# Ethernet.net
KiCad netlist of a schematic drawn in Altium Designer
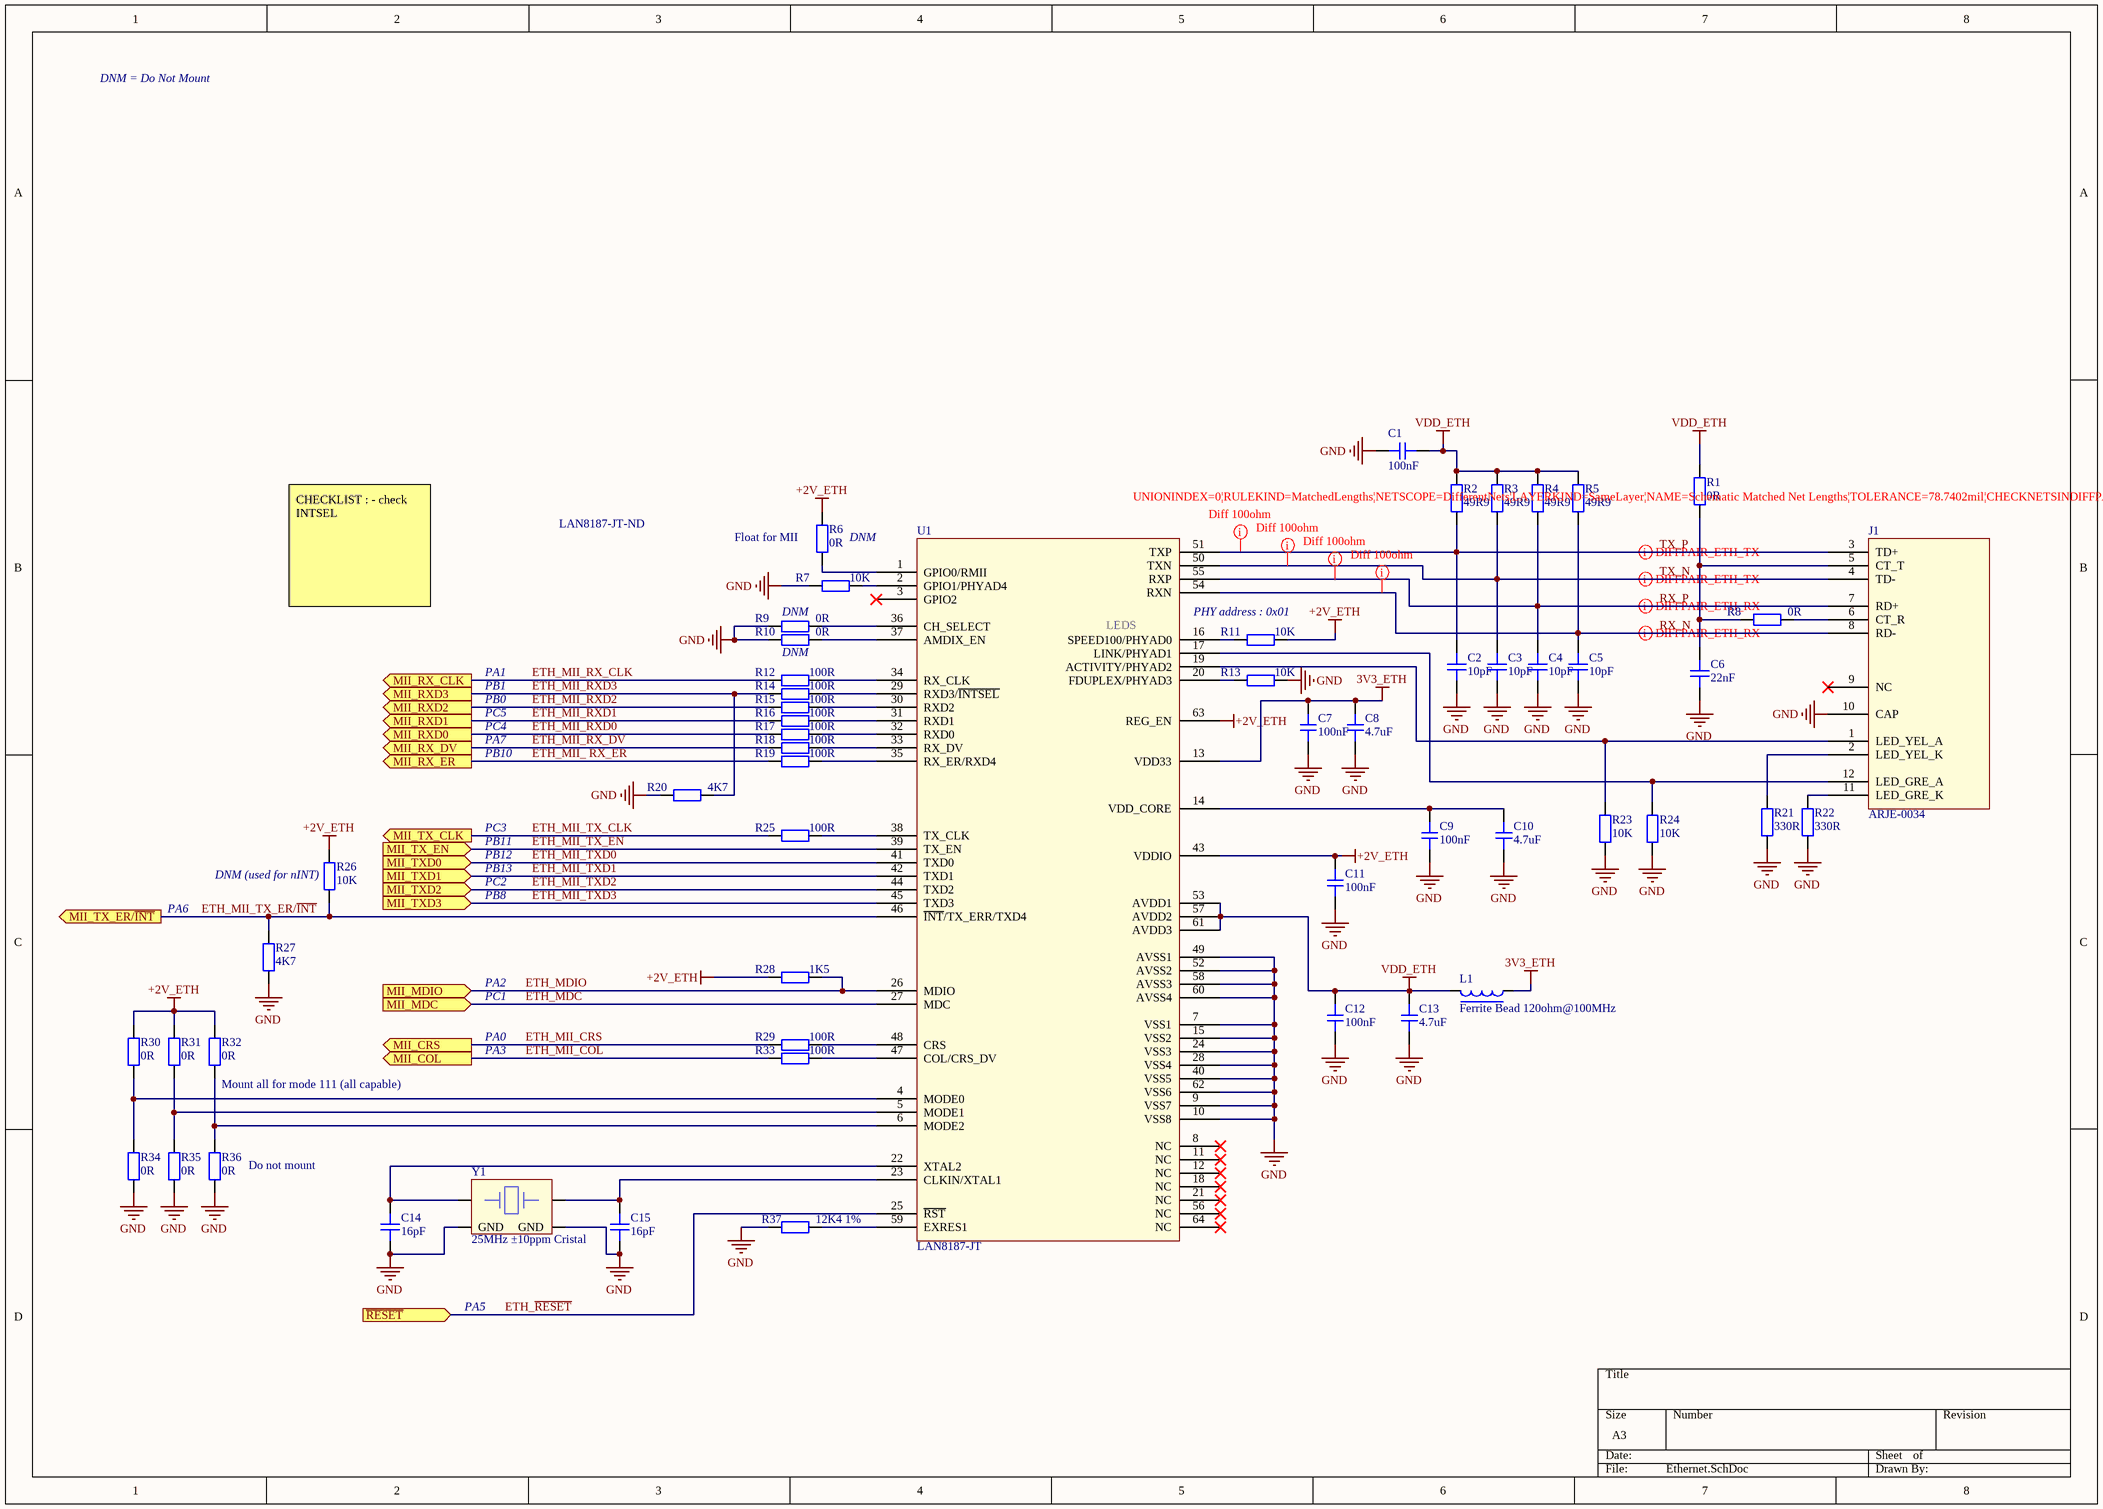
[diagram p0: Ethernet.SchDoc]

(export (version "E")
  (design (tool "Eeschema 10.0.6"))
  (components
    (comp (ref "C1")
      (value "100nF")
      (footprint "Capacitor-0603")
      (fields (field (name "Comment") "C-100nF-0603"))
      (libsource (lib "Components") (part "C-100nF-0603"))
    )
    (comp (ref "C2")
      (value "10pF")
      (footprint "Capacitor-0603")
      (fields (field (name "Comment") "C-10pF-0603"))
      (libsource (lib "Components") (part "C-10pF-0603"))
    )
    (comp (ref "C3")
      (value "10pF")
      (footprint "Capacitor-0603")
      (fields (field (name "Comment") "C-10pF-0603"))
      (libsource (lib "Components") (part "C-10pF-0603"))
    )
    (comp (ref "C4")
      (value "10pF")
      (footprint "Capacitor-0603")
      (fields (field (name "Comment") "C-10pF-0603"))
      (libsource (lib "Components") (part "C-10pF-0603"))
    )
    (comp (ref "C5")
      (value "10pF")
      (footprint "Capacitor-0603")
      (fields (field (name "Comment") "C-10pF-0603"))
      (libsource (lib "Components") (part "C-10pF-0603"))
    )
    (comp (ref "C6")
      (value "22nF")
      (footprint "Capacitor-0603")
      (fields (field (name "Comment") "C-22nF-0603"))
      (libsource (lib "Components") (part "C-22nF-0603"))
    )
    (comp (ref "C7")
      (value "100nF")
      (footprint "Capacitor-0603")
      (fields (field (name "Comment") "C-100nF-0603"))
      (libsource (lib "Components") (part "C-100nF-0603"))
    )
    (comp (ref "C8")
      (value "4.7uF")
      (footprint "Capacitor-0603")
      (fields (field (name "Comment") "C-4.7uF-0603"))
      (libsource (lib "Components") (part "C-4.7uF-0603"))
    )
    (comp (ref "C9")
      (value "100nF")
      (footprint "Capacitor-0603")
      (fields (field (name "Comment") "C-100nF-0603"))
      (libsource (lib "Components") (part "C-100nF-0603"))
    )
    (comp (ref "C10")
      (value "4.7uF")
      (footprint "Capacitor-0603")
      (fields (field (name "Comment") "C-4.7uF-0603"))
      (libsource (lib "Components") (part "C-4.7uF-0603"))
    )
    (comp (ref "C11")
      (value "100nF")
      (footprint "Capacitor-0603")
      (fields (field (name "Comment") "C-100nF-0603"))
      (libsource (lib "Components") (part "C-100nF-0603"))
    )
    (comp (ref "C12")
      (value "100nF")
      (footprint "Capacitor-0603")
      (fields (field (name "Comment") "C-100nF-0603"))
      (libsource (lib "Components") (part "C-100nF-0603"))
    )
    (comp (ref "C13")
      (value "4.7uF")
      (footprint "Capacitor-0603")
      (fields (field (name "Comment") "C-4.7uF-0603"))
      (libsource (lib "Components") (part "C-4.7uF-0603"))
    )
    (comp (ref "C14")
      (value "16pF")
      (footprint "Capacitor-0603")
      (fields (field (name "Comment") "C-16pF-0603"))
      (libsource (lib "Components") (part "C-16pF-0603"))
    )
    (comp (ref "C15")
      (value "16pF")
      (footprint "Capacitor-0603")
      (fields (field (name "Comment") "C-16pF-0603"))
      (libsource (lib "Components") (part "C-16pF-0603"))
    )
    (comp (ref "J1")
      (value "ARJE-0034")
      (footprint "ARJE-0034")
      (libsource (lib "Components") (part "ARJE-0034"))
    )
    (comp (ref "L1")
      (value "Ferrite Bead 120ohm@100MHz")
      (footprint "Inductor-0603")
      (libsource (lib "Components") (part "PE-0603PFB121ST"))
    )
    (comp (ref "R1")
      (value "0R")
      (footprint "Resistor-0603")
      (fields (field (name "Comment") "R-0R-0603"))
      (libsource (lib "Components") (part "R-0R-0603"))
    )
    (comp (ref "R2")
      (value "49R9")
      (footprint "Resistor-0603")
      (fields (field (name "Comment") "R-49R9-0603"))
      (libsource (lib "Components") (part "R-49R9-0603"))
    )
    (comp (ref "R3")
      (value "49R9")
      (footprint "Resistor-0603")
      (fields (field (name "Comment") "R-49R9-0603"))
      (libsource (lib "Components") (part "R-49R9-0603"))
    )
    (comp (ref "R4")
      (value "49R9")
      (footprint "Resistor-0603")
      (fields (field (name "Comment") "R-49R9-0603"))
      (libsource (lib "Components") (part "R-49R9-0603"))
    )
    (comp (ref "R5")
      (value "49R9")
      (footprint "Resistor-0603")
      (fields (field (name "Comment") "R-49R9-0603"))
      (libsource (lib "Components") (part "R-49R9-0603"))
    )
    (comp (ref "R6")
      (value "0R")
      (footprint "Resistor-0603")
      (fields (field (name "Comment") "R-0R-0603"))
      (libsource (lib "Components") (part "R-0R-0603"))
    )
    (comp (ref "R7")
      (value "10K")
      (footprint "Resistor-0603")
      (fields (field (name "Comment") "R-10K-0603"))
      (libsource (lib "Components") (part "R-10K-0603"))
    )
    (comp (ref "R8")
      (value "0R")
      (footprint "Resistor-0603")
      (fields (field (name "Comment") "R-0R-0603"))
      (libsource (lib "Components") (part "R-0R-0603"))
    )
    (comp (ref "R9")
      (value "0R")
      (footprint "Resistor-0603")
      (fields (field (name "Comment") "R-0R-0603"))
      (libsource (lib "Components") (part "R-0R-0603"))
    )
    (comp (ref "R10")
      (value "0R")
      (footprint "Resistor-0603")
      (fields (field (name "Comment") "R-0R-0603"))
      (libsource (lib "Components") (part "R-0R-0603"))
    )
    (comp (ref "R11")
      (value "10K")
      (footprint "Resistor-0603")
      (fields (field (name "Comment") "R-10K-0603"))
      (libsource (lib "Components") (part "R-10K-0603"))
    )
    (comp (ref "R12")
      (value "100R")
      (footprint "Resistor-0603")
      (fields (field (name "Comment") "R-100R-0603"))
      (libsource (lib "Components") (part "R-100R-0603"))
    )
    (comp (ref "R13")
      (value "10K")
      (footprint "Resistor-0603")
      (fields (field (name "Comment") "R-10K-0603"))
      (libsource (lib "Components") (part "R-10K-0603"))
    )
    (comp (ref "R14")
      (value "100R")
      (footprint "Resistor-0603")
      (fields (field (name "Comment") "R-100R-0603"))
      (libsource (lib "Components") (part "R-100R-0603"))
    )
    (comp (ref "R15")
      (value "100R")
      (footprint "Resistor-0603")
      (fields (field (name "Comment") "R-100R-0603"))
      (libsource (lib "Components") (part "R-100R-0603"))
    )
    (comp (ref "R16")
      (value "100R")
      (footprint "Resistor-0603")
      (fields (field (name "Comment") "R-100R-0603"))
      (libsource (lib "Components") (part "R-100R-0603"))
    )
    (comp (ref "R17")
      (value "100R")
      (footprint "Resistor-0603")
      (fields (field (name "Comment") "R-100R-0603"))
      (libsource (lib "Components") (part "R-100R-0603"))
    )
    (comp (ref "R18")
      (value "100R")
      (footprint "Resistor-0603")
      (fields (field (name "Comment") "R-100R-0603"))
      (libsource (lib "Components") (part "R-100R-0603"))
    )
    (comp (ref "R19")
      (value "100R")
      (footprint "Resistor-0603")
      (fields (field (name "Comment") "R-100R-0603"))
      (libsource (lib "Components") (part "R-100R-0603"))
    )
    (comp (ref "R20")
      (value "4K7")
      (footprint "Resistor-0603")
      (fields (field (name "Comment") "R-4K7-0603"))
      (libsource (lib "Components") (part "R-4K7-0603"))
    )
    (comp (ref "R21")
      (value "330R")
      (footprint "Resistor-0603")
      (fields (field (name "Comment") "R-330R-0603"))
      (libsource (lib "Components") (part "R-330R-0603"))
    )
    (comp (ref "R22")
      (value "330R")
      (footprint "Resistor-0603")
      (fields (field (name "Comment") "R-330R-0603"))
      (libsource (lib "Components") (part "R-330R-0603"))
    )
    (comp (ref "R23")
      (value "10K")
      (footprint "Resistor-0603")
      (fields (field (name "Comment") "R-10K-0603"))
      (libsource (lib "Components") (part "R-10K-0603"))
    )
    (comp (ref "R24")
      (value "10K")
      (footprint "Resistor-0603")
      (fields (field (name "Comment") "R-10K-0603"))
      (libsource (lib "Components") (part "R-10K-0603"))
    )
    (comp (ref "R25")
      (value "100R")
      (footprint "Resistor-0603")
      (fields (field (name "Comment") "R-100R-0603"))
      (libsource (lib "Components") (part "R-100R-0603"))
    )
    (comp (ref "R26")
      (value "10K")
      (footprint "Resistor-0603")
      (fields (field (name "Comment") "R-10K-0603"))
      (libsource (lib "Components") (part "R-10K-0603"))
    )
    (comp (ref "R27")
      (value "4K7")
      (footprint "Resistor-0603")
      (fields (field (name "Comment") "R-4K7-0603"))
      (libsource (lib "Components") (part "R-4K7-0603"))
    )
    (comp (ref "R28")
      (value "1K5")
      (footprint "Resistor-0603")
      (fields (field (name "Comment") "R-1K5-0603"))
      (libsource (lib "Components") (part "R-1K5-0603"))
    )
    (comp (ref "R29")
      (value "100R")
      (footprint "Resistor-0603")
      (fields (field (name "Comment") "R-100R-0603"))
      (libsource (lib "Components") (part "R-100R-0603"))
    )
    (comp (ref "R30")
      (value "0R")
      (footprint "Resistor-0603")
      (fields (field (name "Comment") "R-0R-0603"))
      (libsource (lib "Components") (part "R-0R-0603"))
    )
    (comp (ref "R31")
      (value "0R")
      (footprint "Resistor-0603")
      (fields (field (name "Comment") "R-0R-0603"))
      (libsource (lib "Components") (part "R-0R-0603"))
    )
    (comp (ref "R32")
      (value "0R")
      (footprint "Resistor-0603")
      (fields (field (name "Comment") "R-0R-0603"))
      (libsource (lib "Components") (part "R-0R-0603"))
    )
    (comp (ref "R33")
      (value "100R")
      (footprint "Resistor-0603")
      (fields (field (name "Comment") "R-100R-0603"))
      (libsource (lib "Components") (part "R-100R-0603"))
    )
    (comp (ref "R34")
      (value "0R")
      (footprint "Resistor-0603")
      (fields (field (name "Comment") "R-0R-0603"))
      (libsource (lib "Components") (part "R-0R-0603"))
    )
    (comp (ref "R35")
      (value "0R")
      (footprint "Resistor-0603")
      (fields (field (name "Comment") "R-0R-0603"))
      (libsource (lib "Components") (part "R-0R-0603"))
    )
    (comp (ref "R36")
      (value "0R")
      (footprint "Resistor-0603")
      (fields (field (name "Comment") "R-0R-0603"))
      (libsource (lib "Components") (part "R-0R-0603"))
    )
    (comp (ref "R37")
      (value "12K4 1%")
      (footprint "Resistor-0603")
      (fields (field (name "Comment") "R-12K4-1%-0603"))
      (libsource (lib "Components") (part "R-12K4-1%-0603"))
    )
    (comp (ref "U1")
      (value "LAN8187-JT")
      (footprint "LAN8187-JT")
      (fields (field (name "SUPPLIER PART NUMBER 1") "LAN8187-JT-ND"))
      (libsource (lib "Components") (part "LAN8187-JT"))
    )
    (comp (ref "Y1")
      (value "25MHz ±10ppm Cristal")
      (footprint "830107871909")
      (libsource (lib "Components") (part "830107871909"))
    )
  )
  (nets
    (net (code "1") (name "+2V_ETH") (class "Default")
      (node (ref "C11") (pin "2") (pinfunction "2_2") (pintype "passive"))
      (node (ref "R11") (pin "2") (pinfunction "2_2") (pintype "passive"))
      (node (ref "R26") (pin "2") (pinfunction "2_2") (pintype "passive"))
      (node (ref "R28") (pin "1") (pinfunction "1_1") (pintype "passive"))
      (node (ref "R30") (pin "2") (pinfunction "2_2") (pintype "passive"))
      (node (ref "R31") (pin "2") (pinfunction "2_2") (pintype "passive"))
      (node (ref "R32") (pin "2") (pinfunction "2_2") (pintype "passive"))
      (node (ref "R6") (pin "2") (pinfunction "2_2") (pintype "passive"))
      (node (ref "U1") (pin "43") (pinfunction "VDDIO_43") (pintype "passive"))
      (node (ref "U1") (pin "63") (pinfunction "REG_EN_63") (pintype "passive"))
    )
    (net (code "2") (name "/ETH_MDC") (class "Default")
      (node (ref "U1") (pin "27") (pinfunction "MDC_27") (pintype "passive"))
    )
    (net (code "3") (name "/ETH_MDIO") (class "Default")
      (node (ref "R28") (pin "2") (pinfunction "2_2") (pintype "passive"))
      (node (ref "U1") (pin "26") (pinfunction "MDIO_26") (pintype "passive"))
    )
    (net (code "4") (name "/ETH_MII_ RX_ER") (class "Default")
      (node (ref "R19") (pin "1") (pinfunction "1_1") (pintype "passive"))
    )
    (net (code "5") (name "/ETH_MII_COL") (class "Default")
      (node (ref "R33") (pin "1") (pinfunction "1_1") (pintype "passive"))
    )
    (net (code "6") (name "/ETH_MII_CRS") (class "Default")
      (node (ref "R29") (pin "1") (pinfunction "1_1") (pintype "passive"))
    )
    (net (code "7") (name "/ETH_MII_RXD0") (class "Default")
      (node (ref "R17") (pin "1") (pinfunction "1_1") (pintype "passive"))
    )
    (net (code "8") (name "/ETH_MII_RXD1") (class "Default")
      (node (ref "R16") (pin "1") (pinfunction "1_1") (pintype "passive"))
    )
    (net (code "9") (name "/ETH_MII_RXD2") (class "Default")
      (node (ref "R15") (pin "1") (pinfunction "1_1") (pintype "passive"))
    )
    (net (code "10") (name "/ETH_MII_RXD3") (class "Default")
      (node (ref "R14") (pin "1") (pinfunction "1_1") (pintype "passive"))
      (node (ref "R20") (pin "2") (pinfunction "2_2") (pintype "passive"))
    )
    (net (code "11") (name "/ETH_MII_RX_CLK") (class "Default")
      (node (ref "R12") (pin "1") (pinfunction "1_1") (pintype "passive"))
    )
    (net (code "12") (name "/ETH_MII_RX_DV") (class "Default")
      (node (ref "R18") (pin "1") (pinfunction "1_1") (pintype "passive"))
    )
    (net (code "13") (name "/ETH_MII_TXD0") (class "Default")
      (node (ref "U1") (pin "41") (pinfunction "TXD0_41") (pintype "passive"))
    )
    (net (code "14") (name "/ETH_MII_TXD1") (class "Default")
      (node (ref "U1") (pin "42") (pinfunction "TXD1_42") (pintype "passive"))
    )
    (net (code "15") (name "/ETH_MII_TXD2") (class "Default")
      (node (ref "U1") (pin "44") (pinfunction "TXD2_44") (pintype "passive"))
    )
    (net (code "16") (name "/ETH_MII_TXD3") (class "Default")
      (node (ref "U1") (pin "45") (pinfunction "TXD3_45") (pintype "passive"))
    )
    (net (code "17") (name "/ETH_MII_TX_CLK") (class "Default")
      (node (ref "R25") (pin "1") (pinfunction "1_1") (pintype "passive"))
    )
    (net (code "18") (name "/ETH_MII_TX_EN") (class "Default")
      (node (ref "U1") (pin "39") (pinfunction "TX_EN_39") (pintype "passive"))
    )
    (net (code "19") (name "/ETH_MII_TX_ER{slash}~{INT}") (class "Default")
      (node (ref "R26") (pin "1") (pinfunction "1_1") (pintype "passive"))
      (node (ref "R27") (pin "2") (pinfunction "2_2") (pintype "passive"))
      (node (ref "U1") (pin "46") (pinfunction "~{INT}/TX_ERR/TXD4_46") (pintype "passive"))
    )
    (net (code "20") (name "/ETH_~{RESET}") (class "Default")
      (node (ref "U1") (pin "25") (pinfunction "~{RST}_25") (pintype "passive"))
    )
    (net (code "21") (name "/RX_N") (class "Default")
      (node (ref "C5") (pin "2") (pinfunction "2_2") (pintype "passive"))
      (node (ref "J1") (pin "8") (pinfunction "RD-_8") (pintype "passive"))
      (node (ref "R5") (pin "1") (pinfunction "1_1") (pintype "passive"))
      (node (ref "U1") (pin "54") (pinfunction "RXN_54") (pintype "passive"))
    )
    (net (code "22") (name "/RX_P") (class "Default")
      (node (ref "C4") (pin "2") (pinfunction "2_2") (pintype "passive"))
      (node (ref "J1") (pin "7") (pinfunction "RD+_7") (pintype "passive"))
      (node (ref "R4") (pin "1") (pinfunction "1_1") (pintype "passive"))
      (node (ref "U1") (pin "55") (pinfunction "RXP_55") (pintype "passive"))
    )
    (net (code "23") (name "/TX_N") (class "Default")
      (node (ref "C3") (pin "2") (pinfunction "2_2") (pintype "passive"))
      (node (ref "J1") (pin "4") (pinfunction "TD-_4") (pintype "passive"))
      (node (ref "R3") (pin "1") (pinfunction "1_1") (pintype "passive"))
      (node (ref "U1") (pin "50") (pinfunction "TXN_50") (pintype "passive"))
    )
    (net (code "24") (name "/TX_P") (class "Default")
      (node (ref "C2") (pin "2") (pinfunction "2_2") (pintype "passive"))
      (node (ref "J1") (pin "3") (pinfunction "TD+_3") (pintype "passive"))
      (node (ref "R2") (pin "1") (pinfunction "1_1") (pintype "passive"))
      (node (ref "U1") (pin "51") (pinfunction "TXP_51") (pintype "passive"))
    )
    (net (code "25") (name "3V3_ETH") (class "Default")
      (node (ref "C7") (pin "2") (pinfunction "2_2") (pintype "passive"))
      (node (ref "C8") (pin "2") (pinfunction "2_2") (pintype "passive"))
      (node (ref "L1") (pin "2") (pinfunction "2_2") (pintype "passive"))
      (node (ref "U1") (pin "13") (pinfunction "VDD33_13") (pintype "passive"))
    )
    (net (code "26") (name "GND") (class "Default")
      (node (ref "C1") (pin "1") (pinfunction "1_1") (pintype "passive"))
      (node (ref "C10") (pin "1") (pinfunction "1_1") (pintype "passive"))
      (node (ref "C11") (pin "1") (pinfunction "1_1") (pintype "passive"))
      (node (ref "C12") (pin "1") (pinfunction "1_1") (pintype "passive"))
      (node (ref "C13") (pin "1") (pinfunction "1_1") (pintype "passive"))
      (node (ref "C14") (pin "1") (pinfunction "1_1") (pintype "passive"))
      (node (ref "C15") (pin "1") (pinfunction "1_1") (pintype "passive"))
      (node (ref "C2") (pin "1") (pinfunction "1_1") (pintype "passive"))
      (node (ref "C3") (pin "1") (pinfunction "1_1") (pintype "passive"))
      (node (ref "C4") (pin "1") (pinfunction "1_1") (pintype "passive"))
      (node (ref "C5") (pin "1") (pinfunction "1_1") (pintype "passive"))
      (node (ref "C6") (pin "1") (pinfunction "1_1") (pintype "passive"))
      (node (ref "C7") (pin "1") (pinfunction "1_1") (pintype "passive"))
      (node (ref "C8") (pin "1") (pinfunction "1_1") (pintype "passive"))
      (node (ref "C9") (pin "1") (pinfunction "1_1") (pintype "passive"))
      (node (ref "J1") (pin "10") (pinfunction "CAP_10") (pintype "passive"))
      (node (ref "R10") (pin "2") (pinfunction "2_2") (pintype "passive"))
      (node (ref "R13") (pin "2") (pinfunction "2_2") (pintype "passive"))
      (node (ref "R20") (pin "1") (pinfunction "1_1") (pintype "passive"))
      (node (ref "R21") (pin "1") (pinfunction "1_1") (pintype "passive"))
      (node (ref "R22") (pin "1") (pinfunction "1_1") (pintype "passive"))
      (node (ref "R23") (pin "1") (pinfunction "1_1") (pintype "passive"))
      (node (ref "R24") (pin "1") (pinfunction "1_1") (pintype "passive"))
      (node (ref "R27") (pin "1") (pinfunction "1_1") (pintype "passive"))
      (node (ref "R34") (pin "1") (pinfunction "1_1") (pintype "passive"))
      (node (ref "R35") (pin "1") (pinfunction "1_1") (pintype "passive"))
      (node (ref "R36") (pin "1") (pinfunction "1_1") (pintype "passive"))
      (node (ref "R37") (pin "1") (pinfunction "1_1") (pintype "passive"))
      (node (ref "R7") (pin "1") (pinfunction "1_1") (pintype "passive"))
      (node (ref "R9") (pin "2") (pinfunction "2_2") (pintype "passive"))
      (node (ref "U1") (pin "10") (pinfunction "VSS8_10") (pintype "passive"))
      (node (ref "U1") (pin "15") (pinfunction "VSS2_15") (pintype "passive"))
      (node (ref "U1") (pin "24") (pinfunction "VSS3_24") (pintype "passive"))
      (node (ref "U1") (pin "28") (pinfunction "VSS4_28") (pintype "passive"))
      (node (ref "U1") (pin "40") (pinfunction "VSS5_40") (pintype "passive"))
      (node (ref "U1") (pin "49") (pinfunction "AVSS1_49") (pintype "passive"))
      (node (ref "U1") (pin "52") (pinfunction "AVSS2_52") (pintype "passive"))
      (node (ref "U1") (pin "58") (pinfunction "AVSS3_58") (pintype "passive"))
      (node (ref "U1") (pin "60") (pinfunction "AVSS4_60") (pintype "passive"))
      (node (ref "U1") (pin "62") (pinfunction "VSS6_62") (pintype "passive"))
      (node (ref "U1") (pin "7") (pinfunction "VSS1_7") (pintype "passive"))
      (node (ref "U1") (pin "9") (pinfunction "VSS7_9") (pintype "passive"))
      (node (ref "Y1") (pin "2") (pinfunction "GND_2") (pintype "passive"))
      (node (ref "Y1") (pin "4") (pinfunction "GND_4") (pintype "passive"))
    )
    (net (code "27") (name "Net-(J1-CT_R)") (class "Default")
      (node (ref "J1") (pin "6") (pinfunction "CT_R_6") (pintype "passive"))
      (node (ref "R8") (pin "1") (pinfunction "1_1") (pintype "passive"))
    )
    (net (code "28") (name "Net-(J1-CT_T)") (class "Default")
      (node (ref "C6") (pin "2") (pinfunction "2_2") (pintype "passive"))
      (node (ref "J1") (pin "5") (pinfunction "CT_T_5") (pintype "passive"))
      (node (ref "R1") (pin "2") (pinfunction "2_2") (pintype "passive"))
      (node (ref "R8") (pin "2") (pinfunction "2_2") (pintype "passive"))
    )
    (net (code "29") (name "Net-(J1-LED_GRE_A)") (class "Default")
      (node (ref "J1") (pin "12") (pinfunction "LED_GRE_A_12") (pintype "passive"))
      (node (ref "R24") (pin "2") (pinfunction "2_2") (pintype "passive"))
      (node (ref "U1") (pin "17") (pinfunction "LINK/PHYAD1_17") (pintype "passive"))
    )
    (net (code "30") (name "Net-(J1-LED_GRE_K)") (class "Default")
      (node (ref "J1") (pin "11") (pinfunction "LED_GRE_K_11") (pintype "passive"))
      (node (ref "R22") (pin "2") (pinfunction "2_2") (pintype "passive"))
    )
    (net (code "31") (name "Net-(J1-LED_YEL_A)") (class "Default")
      (node (ref "J1") (pin "1") (pinfunction "LED_YEL_A_1") (pintype "passive"))
      (node (ref "R23") (pin "2") (pinfunction "2_2") (pintype "passive"))
      (node (ref "U1") (pin "19") (pinfunction "ACTIVITY/PHYAD2_19") (pintype "passive"))
    )
    (net (code "32") (name "Net-(J1-LED_YEL_K)") (class "Default")
      (node (ref "J1") (pin "2") (pinfunction "LED_YEL_K_2") (pintype "passive"))
      (node (ref "R21") (pin "2") (pinfunction "2_2") (pintype "passive"))
    )
    (net (code "33") (name "Net-(U1-AMDIX_EN)") (class "Default")
      (node (ref "R10") (pin "1") (pinfunction "1_1") (pintype "passive"))
      (node (ref "U1") (pin "37") (pinfunction "AMDIX_EN_37") (pintype "passive"))
    )
    (net (code "34") (name "Net-(U1-CH_SELECT)") (class "Default")
      (node (ref "R9") (pin "1") (pinfunction "1_1") (pintype "passive"))
      (node (ref "U1") (pin "36") (pinfunction "CH_SELECT_36") (pintype "passive"))
    )
    (net (code "35") (name "Net-(U1-CLKIN{slash}XTAL1)") (class "Default")
      (node (ref "C15") (pin "2") (pinfunction "2_2") (pintype "passive"))
      (node (ref "U1") (pin "23") (pinfunction "CLKIN/XTAL1_23") (pintype "passive"))
      (node (ref "Y1") (pin "3") (pinfunction "XTAL2_3") (pintype "passive"))
    )
    (net (code "36") (name "Net-(U1-COL{slash}CRS_DV)") (class "Default")
      (node (ref "R33") (pin "2") (pinfunction "2_2") (pintype "passive"))
      (node (ref "U1") (pin "47") (pinfunction "COL/CRS_DV_47") (pintype "passive"))
    )
    (net (code "37") (name "Net-(U1-CRS)") (class "Default")
      (node (ref "R29") (pin "2") (pinfunction "2_2") (pintype "passive"))
      (node (ref "U1") (pin "48") (pinfunction "CRS_48") (pintype "passive"))
    )
    (net (code "38") (name "Net-(U1-EXRES1)") (class "Default")
      (node (ref "R37") (pin "2") (pinfunction "2_2") (pintype "passive"))
      (node (ref "U1") (pin "59") (pinfunction "EXRES1_59") (pintype "passive"))
    )
    (net (code "39") (name "Net-(U1-FDUPLEX{slash}PHYAD3)") (class "Default")
      (node (ref "R13") (pin "1") (pinfunction "1_1") (pintype "passive"))
      (node (ref "U1") (pin "20") (pinfunction "FDUPLEX/PHYAD3_20") (pintype "passive"))
    )
    (net (code "40") (name "Net-(U1-GPIO0{slash}RMII)") (class "Default")
      (node (ref "R6") (pin "1") (pinfunction "1_1") (pintype "passive"))
      (node (ref "U1") (pin "1") (pinfunction "GPIO0/RMII_1") (pintype "passive"))
    )
    (net (code "41") (name "Net-(U1-GPIO1{slash}PHYAD4)") (class "Default")
      (node (ref "R7") (pin "2") (pinfunction "2_2") (pintype "passive"))
      (node (ref "U1") (pin "2") (pinfunction "GPIO1/PHYAD4_2") (pintype "passive"))
    )
    (net (code "42") (name "Net-(U1-MODE0)") (class "Default")
      (node (ref "R30") (pin "1") (pinfunction "1_1") (pintype "passive"))
      (node (ref "R34") (pin "2") (pinfunction "2_2") (pintype "passive"))
      (node (ref "U1") (pin "4") (pinfunction "MODE0_4") (pintype "passive"))
    )
    (net (code "43") (name "Net-(U1-MODE1)") (class "Default")
      (node (ref "R31") (pin "1") (pinfunction "1_1") (pintype "passive"))
      (node (ref "R35") (pin "2") (pinfunction "2_2") (pintype "passive"))
      (node (ref "U1") (pin "5") (pinfunction "MODE1_5") (pintype "passive"))
    )
    (net (code "44") (name "Net-(U1-MODE2)") (class "Default")
      (node (ref "R32") (pin "1") (pinfunction "1_1") (pintype "passive"))
      (node (ref "R36") (pin "2") (pinfunction "2_2") (pintype "passive"))
      (node (ref "U1") (pin "6") (pinfunction "MODE2_6") (pintype "passive"))
    )
    (net (code "45") (name "Net-(U1-RXD0)") (class "Default")
      (node (ref "R17") (pin "2") (pinfunction "2_2") (pintype "passive"))
      (node (ref "U1") (pin "32") (pinfunction "RXD0_32") (pintype "passive"))
    )
    (net (code "46") (name "Net-(U1-RXD1)") (class "Default")
      (node (ref "R16") (pin "2") (pinfunction "2_2") (pintype "passive"))
      (node (ref "U1") (pin "31") (pinfunction "RXD1_31") (pintype "passive"))
    )
    (net (code "47") (name "Net-(U1-RXD2)") (class "Default")
      (node (ref "R15") (pin "2") (pinfunction "2_2") (pintype "passive"))
      (node (ref "U1") (pin "30") (pinfunction "RXD2_30") (pintype "passive"))
    )
    (net (code "48") (name "Net-(U1-RXD3{slash}~{INTSEL})") (class "Default")
      (node (ref "R14") (pin "2") (pinfunction "2_2") (pintype "passive"))
      (node (ref "U1") (pin "29") (pinfunction "RXD3/~{INTSEL}_29") (pintype "passive"))
    )
    (net (code "49") (name "Net-(U1-RX_CLK)") (class "Default")
      (node (ref "R12") (pin "2") (pinfunction "2_2") (pintype "passive"))
      (node (ref "U1") (pin "34") (pinfunction "RX_CLK_34") (pintype "passive"))
    )
    (net (code "50") (name "Net-(U1-RX_DV)") (class "Default")
      (node (ref "R18") (pin "2") (pinfunction "2_2") (pintype "passive"))
      (node (ref "U1") (pin "33") (pinfunction "RX_DV_33") (pintype "passive"))
    )
    (net (code "51") (name "Net-(U1-RX_ER{slash}RXD4)") (class "Default")
      (node (ref "R19") (pin "2") (pinfunction "2_2") (pintype "passive"))
      (node (ref "U1") (pin "35") (pinfunction "RX_ER/RXD4_35") (pintype "passive"))
    )
    (net (code "52") (name "Net-(U1-SPEED100{slash}PHYAD0)") (class "Default")
      (node (ref "R11") (pin "1") (pinfunction "1_1") (pintype "passive"))
      (node (ref "U1") (pin "16") (pinfunction "SPEED100/PHYAD0_16") (pintype "passive"))
    )
    (net (code "53") (name "Net-(U1-TX_CLK)") (class "Default")
      (node (ref "R25") (pin "2") (pinfunction "2_2") (pintype "passive"))
      (node (ref "U1") (pin "38") (pinfunction "TX_CLK_38") (pintype "passive"))
    )
    (net (code "54") (name "Net-(U1-VDD_CORE)") (class "Default")
      (node (ref "C10") (pin "2") (pinfunction "2_2") (pintype "passive"))
      (node (ref "C9") (pin "2") (pinfunction "2_2") (pintype "passive"))
      (node (ref "U1") (pin "14") (pinfunction "VDD_CORE_14") (pintype "passive"))
    )
    (net (code "55") (name "Net-(U1-XTAL2)") (class "Default")
      (node (ref "C14") (pin "2") (pinfunction "2_2") (pintype "passive"))
      (node (ref "U1") (pin "22") (pinfunction "XTAL2_22") (pintype "passive"))
      (node (ref "Y1") (pin "1") (pinfunction "GND_1") (pintype "passive"))
    )
    (net (code "56") (name "VDD_ETH") (class "Default")
      (node (ref "C1") (pin "2") (pinfunction "2_2") (pintype "passive"))
      (node (ref "C12") (pin "2") (pinfunction "2_2") (pintype "passive"))
      (node (ref "C13") (pin "2") (pinfunction "2_2") (pintype "passive"))
      (node (ref "L1") (pin "1") (pinfunction "1_1") (pintype "passive"))
      (node (ref "R1") (pin "1") (pinfunction "1_1") (pintype "passive"))
      (node (ref "R2") (pin "2") (pinfunction "2_2") (pintype "passive"))
      (node (ref "R3") (pin "2") (pinfunction "2_2") (pintype "passive"))
      (node (ref "R4") (pin "2") (pinfunction "2_2") (pintype "passive"))
      (node (ref "R5") (pin "2") (pinfunction "2_2") (pintype "passive"))
      (node (ref "U1") (pin "53") (pinfunction "AVDD1_53") (pintype "passive"))
      (node (ref "U1") (pin "57") (pinfunction "AVDD2_57") (pintype "passive"))
      (node (ref "U1") (pin "61") (pinfunction "AVDD3_61") (pintype "passive"))
    )
    (net (code "57") (name "unconnected-(J1-NC-Pad9)") (class "Default")
      (node (ref "J1") (pin "9") (pinfunction "NC_9") (pintype "passive+no_connect"))
    )
    (net (code "58") (name "unconnected-(U1-GPIO2-Pad3)") (class "Default")
      (node (ref "U1") (pin "3") (pinfunction "GPIO2_3") (pintype "passive+no_connect"))
    )
    (net (code "59") (name "unconnected-(U1-NC-Pad8)") (class "Default")
      (node (ref "U1") (pin "8") (pinfunction "NC_8") (pintype "passive+no_connect"))
    )
    (net (code "60") (name "unconnected-(U1-NC-Pad11)") (class "Default")
      (node (ref "U1") (pin "11") (pinfunction "NC_11") (pintype "passive+no_connect"))
    )
    (net (code "61") (name "unconnected-(U1-NC-Pad12)") (class "Default")
      (node (ref "U1") (pin "12") (pinfunction "NC_12") (pintype "passive+no_connect"))
    )
    (net (code "62") (name "unconnected-(U1-NC-Pad18)") (class "Default")
      (node (ref "U1") (pin "18") (pinfunction "NC_18") (pintype "passive+no_connect"))
    )
    (net (code "63") (name "unconnected-(U1-NC-Pad21)") (class "Default")
      (node (ref "U1") (pin "21") (pinfunction "NC_21") (pintype "passive+no_connect"))
    )
    (net (code "64") (name "unconnected-(U1-NC-Pad56)") (class "Default")
      (node (ref "U1") (pin "56") (pinfunction "NC_56") (pintype "passive+no_connect"))
    )
    (net (code "65") (name "unconnected-(U1-NC-Pad64)") (class "Default")
      (node (ref "U1") (pin "64") (pinfunction "NC_64") (pintype "passive+no_connect"))
    )
  )
)
